# B204D.net
KiCad netlist of a schematic drawn in EAGLE
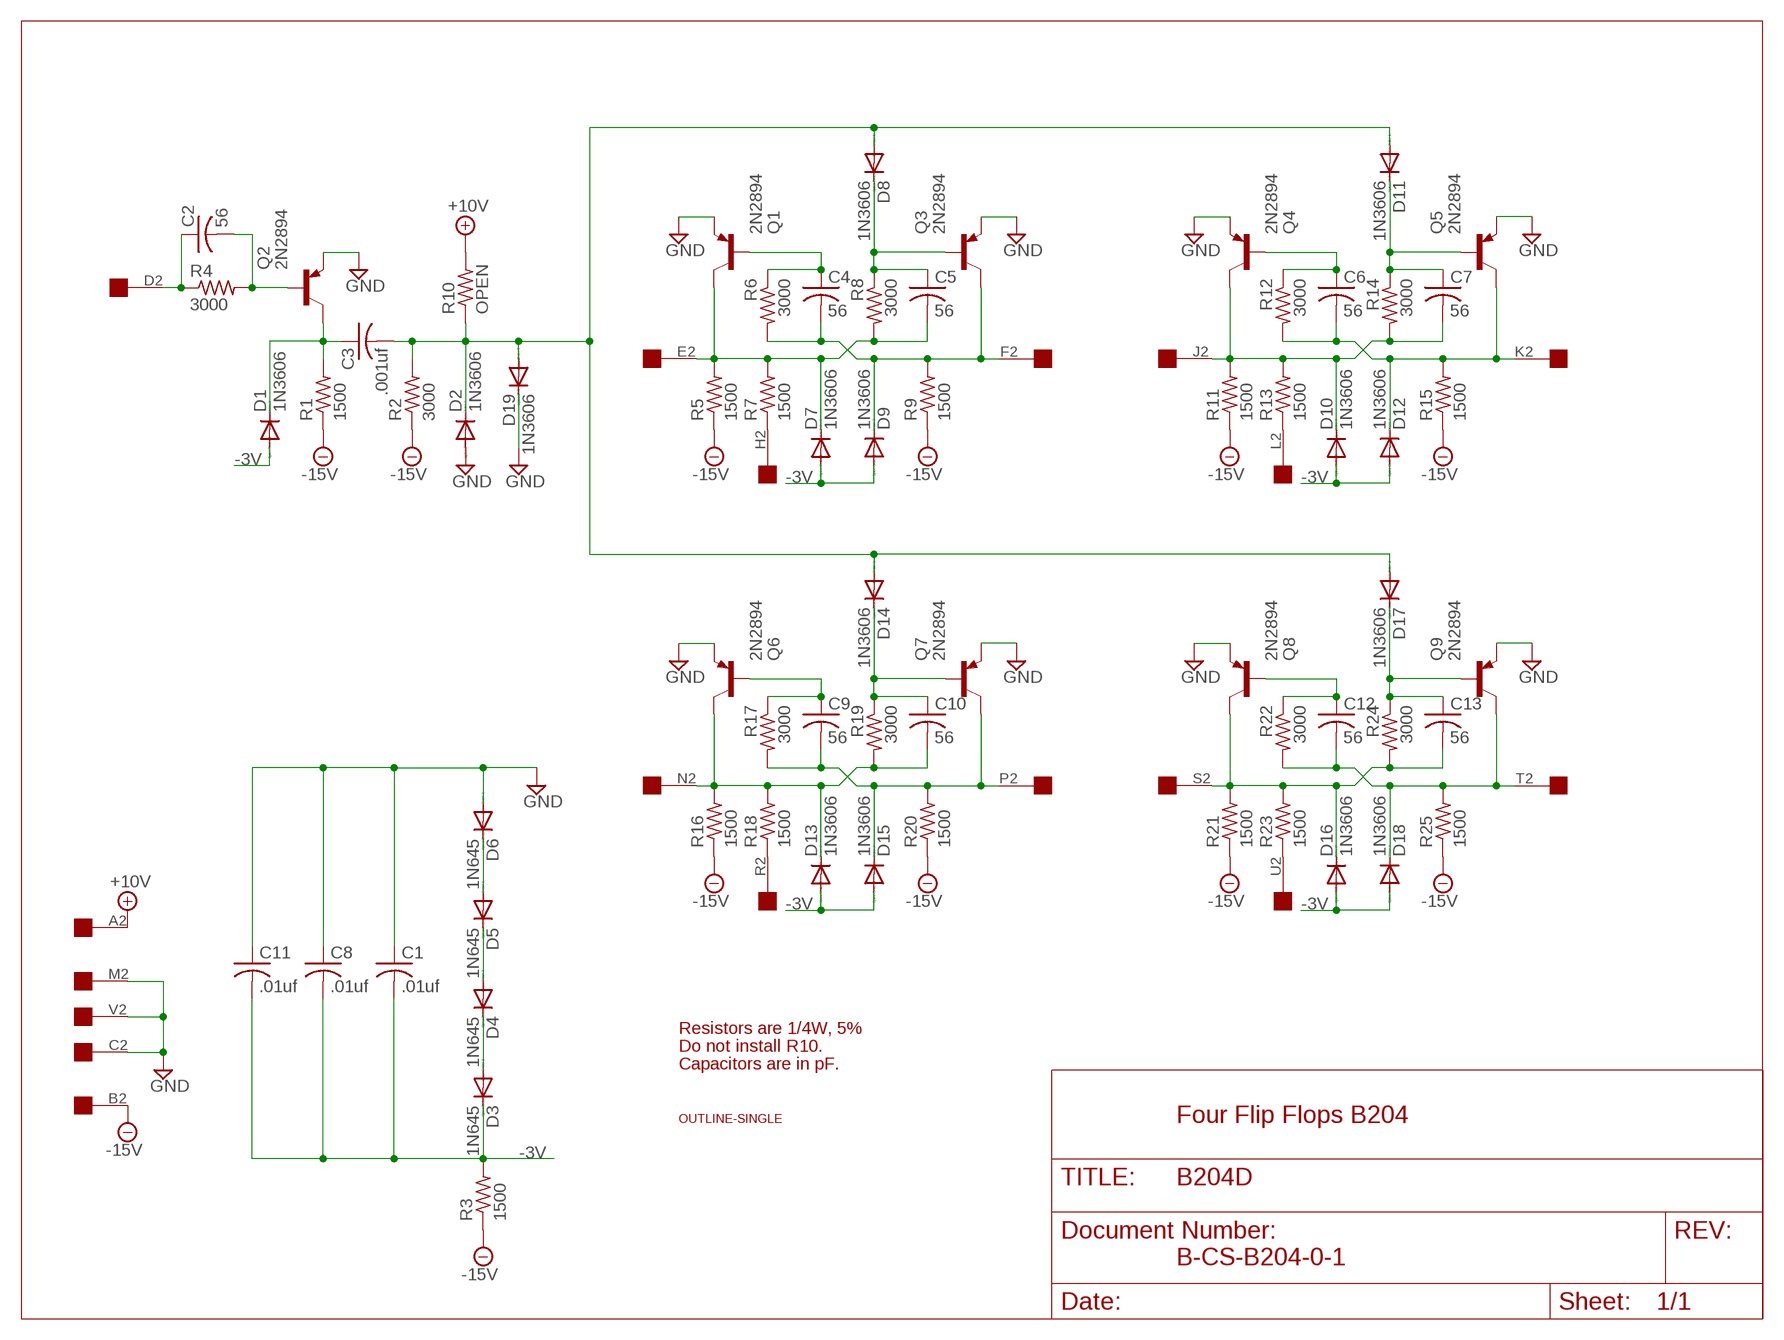
[diagram p0: schematic, sheet 1]

(export (version "E")
  (design (tool "Eeschema 10.0.6"))
  (components
    (comp (ref "C1")
      (value ".01uf")
      (footprint "eagle-import:C050-025X075")
      (libsource (lib "eagle-import") (part "C-US050-025X075"))
    )
    (comp (ref "C2")
      (value "56")
      (footprint "eagle-import:C075-032X103")
      (libsource (lib "eagle-import") (part "C-US075-032X103"))
    )
    (comp (ref "C3")
      (value ".001uf")
      (footprint "eagle-import:C050-025X075")
      (libsource (lib "eagle-import") (part "C-US050-025X075"))
    )
    (comp (ref "C4")
      (value "56")
      (footprint "eagle-import:C075-032X103")
      (libsource (lib "eagle-import") (part "C-US075-032X103"))
    )
    (comp (ref "C5")
      (value "56")
      (footprint "eagle-import:C075-032X103")
      (libsource (lib "eagle-import") (part "C-US075-032X103"))
    )
    (comp (ref "C6")
      (value "56")
      (footprint "eagle-import:C075-032X103")
      (libsource (lib "eagle-import") (part "C-US075-032X103"))
    )
    (comp (ref "C7")
      (value "56")
      (footprint "eagle-import:C075-032X103")
      (libsource (lib "eagle-import") (part "C-US075-032X103"))
    )
    (comp (ref "C8")
      (value ".01uf")
      (footprint "eagle-import:C050-025X075")
      (libsource (lib "eagle-import") (part "C-US050-025X075"))
    )
    (comp (ref "C9")
      (value "56")
      (footprint "eagle-import:C075-032X103")
      (libsource (lib "eagle-import") (part "C-US075-032X103"))
    )
    (comp (ref "C10")
      (value "56")
      (footprint "eagle-import:C075-032X103")
      (libsource (lib "eagle-import") (part "C-US075-032X103"))
    )
    (comp (ref "C11")
      (value ".01uf")
      (footprint "eagle-import:C050-025X075")
      (libsource (lib "eagle-import") (part "C-US050-025X075"))
    )
    (comp (ref "C12")
      (value "56")
      (footprint "eagle-import:C075-032X103")
      (libsource (lib "eagle-import") (part "C-US075-032X103"))
    )
    (comp (ref "C13")
      (value "56")
      (footprint "eagle-import:C075-032X103")
      (libsource (lib "eagle-import") (part "C-US075-032X103"))
    )
    (comp (ref "D1")
      (value "1N3606")
      (footprint "eagle-import:DO35-10")
      (libsource (lib "eagle-import") (part "1N4148DO35-10"))
    )
    (comp (ref "D2")
      (value "1N3606")
      (footprint "eagle-import:DO35-10")
      (libsource (lib "eagle-import") (part "1N4148DO35-10"))
    )
    (comp (ref "D3")
      (value "1N645")
      (footprint "eagle-import:DO35-10")
      (libsource (lib "eagle-import") (part "1N4148DO35-10"))
    )
    (comp (ref "D4")
      (value "1N645")
      (footprint "eagle-import:DO35-10")
      (libsource (lib "eagle-import") (part "1N4148DO35-10"))
    )
    (comp (ref "D5")
      (value "1N645")
      (footprint "eagle-import:DO35-10")
      (libsource (lib "eagle-import") (part "1N4148DO35-10"))
    )
    (comp (ref "D6")
      (value "1N645")
      (footprint "eagle-import:DO35-10")
      (libsource (lib "eagle-import") (part "1N4148DO35-10"))
    )
    (comp (ref "D7")
      (value "1N3606")
      (footprint "eagle-import:DO35-10")
      (libsource (lib "eagle-import") (part "1N4148DO35-10"))
    )
    (comp (ref "D8")
      (value "1N3606")
      (footprint "eagle-import:DO35-10")
      (libsource (lib "eagle-import") (part "1N4148DO35-10"))
    )
    (comp (ref "D9")
      (value "1N3606")
      (footprint "eagle-import:DO35-10")
      (libsource (lib "eagle-import") (part "1N4148DO35-10"))
    )
    (comp (ref "D10")
      (value "1N3606")
      (footprint "eagle-import:DO35-10")
      (libsource (lib "eagle-import") (part "1N4148DO35-10"))
    )
    (comp (ref "D11")
      (value "1N3606")
      (footprint "eagle-import:DO35-10")
      (libsource (lib "eagle-import") (part "1N4148DO35-10"))
    )
    (comp (ref "D12")
      (value "1N3606")
      (footprint "eagle-import:DO35-10")
      (libsource (lib "eagle-import") (part "1N4148DO35-10"))
    )
    (comp (ref "D13")
      (value "1N3606")
      (footprint "eagle-import:DO35-10")
      (libsource (lib "eagle-import") (part "1N4148DO35-10"))
    )
    (comp (ref "D14")
      (value "1N3606")
      (footprint "eagle-import:DO35-10")
      (libsource (lib "eagle-import") (part "1N4148DO35-10"))
    )
    (comp (ref "D15")
      (value "1N3606")
      (footprint "eagle-import:DO35-10")
      (libsource (lib "eagle-import") (part "1N4148DO35-10"))
    )
    (comp (ref "D16")
      (value "1N3606")
      (footprint "eagle-import:DO35-10")
      (libsource (lib "eagle-import") (part "1N4148DO35-10"))
    )
    (comp (ref "D17")
      (value "1N3606")
      (footprint "eagle-import:DO35-10")
      (libsource (lib "eagle-import") (part "1N4148DO35-10"))
    )
    (comp (ref "D18")
      (value "1N3606")
      (footprint "eagle-import:DO35-10")
      (libsource (lib "eagle-import") (part "1N4148DO35-10"))
    )
    (comp (ref "D19")
      (value "1N3606")
      (footprint "eagle-import:DO35-10")
      (libsource (lib "eagle-import") (part "1N4148DO35-10"))
    )
    (comp (ref "Q1")
      (value "2N2894")
      (footprint "eagle-import:TO39")
      (libsource (lib "eagle-import") (part "2N3637"))
    )
    (comp (ref "Q2")
      (value "2N2894")
      (footprint "eagle-import:TO39")
      (libsource (lib "eagle-import") (part "2N3637"))
    )
    (comp (ref "Q3")
      (value "2N2894")
      (footprint "eagle-import:TO39")
      (libsource (lib "eagle-import") (part "2N3637"))
    )
    (comp (ref "Q4")
      (value "2N2894")
      (footprint "eagle-import:TO39")
      (libsource (lib "eagle-import") (part "2N3637"))
    )
    (comp (ref "Q5")
      (value "2N2894")
      (footprint "eagle-import:TO39")
      (libsource (lib "eagle-import") (part "2N3637"))
    )
    (comp (ref "Q6")
      (value "2N2894")
      (footprint "eagle-import:TO39")
      (libsource (lib "eagle-import") (part "2N3637"))
    )
    (comp (ref "Q7")
      (value "2N2894")
      (footprint "eagle-import:TO39")
      (libsource (lib "eagle-import") (part "2N3637"))
    )
    (comp (ref "Q8")
      (value "2N2894")
      (footprint "eagle-import:TO39")
      (libsource (lib "eagle-import") (part "2N3637"))
    )
    (comp (ref "Q9")
      (value "2N2894")
      (footprint "eagle-import:TO39")
      (libsource (lib "eagle-import") (part "2N3637"))
    )
    (comp (ref "R1")
      (value "1500")
      (footprint "eagle-import:0207_10")
      (libsource (lib "eagle-import") (part "R-US_0207/10"))
    )
    (comp (ref "R2")
      (value "3000")
      (footprint "eagle-import:0207_10")
      (libsource (lib "eagle-import") (part "R-US_0207/10"))
    )
    (comp (ref "R3")
      (value "1500")
      (footprint "eagle-import:0207_10")
      (libsource (lib "eagle-import") (part "R-US_0207/10"))
    )
    (comp (ref "R4")
      (value "3000")
      (footprint "eagle-import:0207_10")
      (libsource (lib "eagle-import") (part "R-US_0207/10"))
    )
    (comp (ref "R5")
      (value "1500")
      (footprint "eagle-import:0207_10")
      (libsource (lib "eagle-import") (part "R-US_0207/10"))
    )
    (comp (ref "R6")
      (value "3000")
      (footprint "eagle-import:0207_10")
      (libsource (lib "eagle-import") (part "R-US_0207/10"))
    )
    (comp (ref "R7")
      (value "1500")
      (footprint "eagle-import:0207_10")
      (libsource (lib "eagle-import") (part "R-US_0207/10"))
    )
    (comp (ref "R8")
      (value "3000")
      (footprint "eagle-import:0207_10")
      (libsource (lib "eagle-import") (part "R-US_0207/10"))
    )
    (comp (ref "R9")
      (value "1500")
      (footprint "eagle-import:0207_10")
      (libsource (lib "eagle-import") (part "R-US_0207/10"))
    )
    (comp (ref "R10")
      (value "OPEN")
      (footprint "eagle-import:0207_10")
      (libsource (lib "eagle-import") (part "R-US_0207/10"))
    )
    (comp (ref "R11")
      (value "1500")
      (footprint "eagle-import:0207_10")
      (libsource (lib "eagle-import") (part "R-US_0207/10"))
    )
    (comp (ref "R12")
      (value "3000")
      (footprint "eagle-import:0207_10")
      (libsource (lib "eagle-import") (part "R-US_0207/10"))
    )
    (comp (ref "R13")
      (value "1500")
      (footprint "eagle-import:0207_10")
      (libsource (lib "eagle-import") (part "R-US_0207/10"))
    )
    (comp (ref "R14")
      (value "3000")
      (footprint "eagle-import:0207_10")
      (libsource (lib "eagle-import") (part "R-US_0207/10"))
    )
    (comp (ref "R15")
      (value "1500")
      (footprint "eagle-import:0207_10")
      (libsource (lib "eagle-import") (part "R-US_0207/10"))
    )
    (comp (ref "R16")
      (value "1500")
      (footprint "eagle-import:0207_10")
      (libsource (lib "eagle-import") (part "R-US_0207/10"))
    )
    (comp (ref "R17")
      (value "3000")
      (footprint "eagle-import:0207_10")
      (libsource (lib "eagle-import") (part "R-US_0207/10"))
    )
    (comp (ref "R18")
      (value "1500")
      (footprint "eagle-import:0207_10")
      (libsource (lib "eagle-import") (part "R-US_0207/10"))
    )
    (comp (ref "R19")
      (value "3000")
      (footprint "eagle-import:0207_10")
      (libsource (lib "eagle-import") (part "R-US_0207/10"))
    )
    (comp (ref "R20")
      (value "1500")
      (footprint "eagle-import:0207_10")
      (libsource (lib "eagle-import") (part "R-US_0207/10"))
    )
    (comp (ref "R21")
      (value "1500")
      (footprint "eagle-import:0207_10")
      (libsource (lib "eagle-import") (part "R-US_0207/10"))
    )
    (comp (ref "R22")
      (value "3000")
      (footprint "eagle-import:0207_10")
      (libsource (lib "eagle-import") (part "R-US_0207/10"))
    )
    (comp (ref "R23")
      (value "1500")
      (footprint "eagle-import:0207_10")
      (libsource (lib "eagle-import") (part "R-US_0207/10"))
    )
    (comp (ref "R24")
      (value "3000")
      (footprint "eagle-import:0207_10")
      (libsource (lib "eagle-import") (part "R-US_0207/10"))
    )
    (comp (ref "R25")
      (value "1500")
      (footprint "eagle-import:0207_10")
      (libsource (lib "eagle-import") (part "R-US_0207/10"))
    )
    (comp (ref "U$1")
      (value "OUTLINE-SINGLE")
      (footprint "eagle-import:SINGLE")
      (libsource (lib "eagle-import") (part "OUTLINE-SINGLE"))
    )
    (comp (ref "U$2")
      (value "EDGE-1")
      (footprint "eagle-import:EDGE-CON1")
      (libsource (lib "eagle-import") (part "EDGE-1"))
    )
  )
  (nets
    (net (code "1") (name "+10V") (class "Default")
      (node (ref "R10") (pin "2") (pinfunction "2_2") (pintype "passive"))
      (node (ref "U$2") (pin "A2") (pinfunction "1_A2") (pintype "bidirectional"))
    )
    (net (code "2") (name "-15V") (class "Default")
      (node (ref "R1") (pin "1") (pinfunction "1_1") (pintype "passive"))
      (node (ref "R11") (pin "1") (pinfunction "1_1") (pintype "passive"))
      (node (ref "R15") (pin "1") (pinfunction "1_1") (pintype "passive"))
      (node (ref "R16") (pin "1") (pinfunction "1_1") (pintype "passive"))
      (node (ref "R2") (pin "1") (pinfunction "1_1") (pintype "passive"))
      (node (ref "R20") (pin "1") (pinfunction "1_1") (pintype "passive"))
      (node (ref "R21") (pin "1") (pinfunction "1_1") (pintype "passive"))
      (node (ref "R25") (pin "1") (pinfunction "1_1") (pintype "passive"))
      (node (ref "R3") (pin "1") (pinfunction "1_1") (pintype "passive"))
      (node (ref "R5") (pin "1") (pinfunction "1_1") (pintype "passive"))
      (node (ref "R9") (pin "1") (pinfunction "1_1") (pintype "passive"))
      (node (ref "U$2") (pin "B2") (pinfunction "1_B2") (pintype "bidirectional"))
    )
    (net (code "3") (name "/-3V") (class "Default")
      (node (ref "C1") (pin "2") (pinfunction "2_2") (pintype "passive"))
      (node (ref "C11") (pin "2") (pinfunction "2_2") (pintype "passive"))
      (node (ref "C8") (pin "2") (pinfunction "2_2") (pintype "passive"))
      (node (ref "D1") (pin "A") (pinfunction "A_A") (pintype "passive"))
      (node (ref "D10") (pin "A") (pinfunction "A_A") (pintype "passive"))
      (node (ref "D12") (pin "A") (pinfunction "A_A") (pintype "passive"))
      (node (ref "D13") (pin "A") (pinfunction "A_A") (pintype "passive"))
      (node (ref "D15") (pin "A") (pinfunction "A_A") (pintype "passive"))
      (node (ref "D16") (pin "A") (pinfunction "A_A") (pintype "passive"))
      (node (ref "D18") (pin "A") (pinfunction "A_A") (pintype "passive"))
      (node (ref "D3") (pin "C") (pinfunction "C_C") (pintype "passive"))
      (node (ref "D7") (pin "A") (pinfunction "A_A") (pintype "passive"))
      (node (ref "D9") (pin "A") (pinfunction "A_A") (pintype "passive"))
      (node (ref "R3") (pin "2") (pinfunction "2_2") (pintype "passive"))
    )
    (net (code "4") (name "GND") (class "Default")
      (node (ref "C1") (pin "1") (pinfunction "1_1") (pintype "passive"))
      (node (ref "C11") (pin "1") (pinfunction "1_1") (pintype "passive"))
      (node (ref "C8") (pin "1") (pinfunction "1_1") (pintype "passive"))
      (node (ref "D19") (pin "C") (pinfunction "C_C") (pintype "passive"))
      (node (ref "D2") (pin "A") (pinfunction "A_A") (pintype "passive"))
      (node (ref "D6") (pin "A") (pinfunction "A_A") (pintype "passive"))
      (node (ref "Q1") (pin "1") (pinfunction "E_1") (pintype "passive"))
      (node (ref "Q2") (pin "1") (pinfunction "E_1") (pintype "passive"))
      (node (ref "Q3") (pin "1") (pinfunction "E_1") (pintype "passive"))
      (node (ref "Q4") (pin "1") (pinfunction "E_1") (pintype "passive"))
      (node (ref "Q5") (pin "1") (pinfunction "E_1") (pintype "passive"))
      (node (ref "Q6") (pin "1") (pinfunction "E_1") (pintype "passive"))
      (node (ref "Q7") (pin "1") (pinfunction "E_1") (pintype "passive"))
      (node (ref "Q8") (pin "1") (pinfunction "E_1") (pintype "passive"))
      (node (ref "Q9") (pin "1") (pinfunction "E_1") (pintype "passive"))
      (node (ref "U$2") (pin "C2") (pinfunction "1_C2") (pintype "bidirectional"))
      (node (ref "U$2") (pin "M2") (pinfunction "1_M2") (pintype "bidirectional"))
      (node (ref "U$2") (pin "V2") (pinfunction "1_V2") (pintype "bidirectional"))
    )
    (net (code "5") (name "Net-(C3-Pad2)") (class "Default")
      (node (ref "C3") (pin "2") (pinfunction "2_2") (pintype "passive"))
      (node (ref "D11") (pin "A") (pinfunction "A_A") (pintype "passive"))
      (node (ref "D14") (pin "A") (pinfunction "A_A") (pintype "passive"))
      (node (ref "D17") (pin "A") (pinfunction "A_A") (pintype "passive"))
      (node (ref "D19") (pin "A") (pinfunction "A_A") (pintype "passive"))
      (node (ref "D2") (pin "C") (pinfunction "C_C") (pintype "passive"))
      (node (ref "D8") (pin "A") (pinfunction "A_A") (pintype "passive"))
      (node (ref "R10") (pin "1") (pinfunction "1_1") (pintype "passive"))
      (node (ref "R2") (pin "2") (pinfunction "2_2") (pintype "passive"))
    )
    (net (code "6") (name "Net-(D3-PadA)") (class "Default")
      (node (ref "D3") (pin "A") (pinfunction "A_A") (pintype "passive"))
      (node (ref "D4") (pin "C") (pinfunction "C_C") (pintype "passive"))
    )
    (net (code "7") (name "Net-(D4-PadA)") (class "Default")
      (node (ref "D4") (pin "A") (pinfunction "A_A") (pintype "passive"))
      (node (ref "D5") (pin "C") (pinfunction "C_C") (pintype "passive"))
    )
    (net (code "8") (name "Net-(D5-PadA)") (class "Default")
      (node (ref "D5") (pin "A") (pinfunction "A_A") (pintype "passive"))
      (node (ref "D6") (pin "C") (pinfunction "C_C") (pintype "passive"))
    )
    (net (code "9") (name "Net-(Q1-B)") (class "Default")
      (node (ref "C4") (pin "1") (pinfunction "1_1") (pintype "passive"))
      (node (ref "Q1") (pin "2") (pinfunction "B_2") (pintype "passive"))
      (node (ref "R6") (pin "1") (pinfunction "1_1") (pintype "passive"))
    )
    (net (code "10") (name "Net-(Q1-C)") (class "Default")
      (node (ref "C5") (pin "2") (pinfunction "2_2") (pintype "passive"))
      (node (ref "D7") (pin "C") (pinfunction "C_C") (pintype "passive"))
      (node (ref "Q1") (pin "3") (pinfunction "C_3") (pintype "passive"))
      (node (ref "R5") (pin "2") (pinfunction "2_2") (pintype "passive"))
      (node (ref "R7") (pin "2") (pinfunction "2_2") (pintype "passive"))
      (node (ref "R8") (pin "2") (pinfunction "2_2") (pintype "passive"))
      (node (ref "U$2") (pin "E2") (pinfunction "1_E2") (pintype "bidirectional"))
    )
    (net (code "11") (name "Net-(Q2-B)") (class "Default")
      (node (ref "C2") (pin "2") (pinfunction "2_2") (pintype "passive"))
      (node (ref "Q2") (pin "2") (pinfunction "B_2") (pintype "passive"))
      (node (ref "R4") (pin "2") (pinfunction "2_2") (pintype "passive"))
    )
    (net (code "12") (name "Net-(Q2-C)") (class "Default")
      (node (ref "C3") (pin "1") (pinfunction "1_1") (pintype "passive"))
      (node (ref "D1") (pin "C") (pinfunction "C_C") (pintype "passive"))
      (node (ref "Q2") (pin "3") (pinfunction "C_3") (pintype "passive"))
      (node (ref "R1") (pin "2") (pinfunction "2_2") (pintype "passive"))
    )
    (net (code "13") (name "Net-(Q3-B)") (class "Default")
      (node (ref "C5") (pin "1") (pinfunction "1_1") (pintype "passive"))
      (node (ref "D8") (pin "C") (pinfunction "C_C") (pintype "passive"))
      (node (ref "Q3") (pin "2") (pinfunction "B_2") (pintype "passive"))
      (node (ref "R8") (pin "1") (pinfunction "1_1") (pintype "passive"))
    )
    (net (code "14") (name "Net-(Q3-C)") (class "Default")
      (node (ref "C4") (pin "2") (pinfunction "2_2") (pintype "passive"))
      (node (ref "D9") (pin "C") (pinfunction "C_C") (pintype "passive"))
      (node (ref "Q3") (pin "3") (pinfunction "C_3") (pintype "passive"))
      (node (ref "R6") (pin "2") (pinfunction "2_2") (pintype "passive"))
      (node (ref "R9") (pin "2") (pinfunction "2_2") (pintype "passive"))
      (node (ref "U$2") (pin "F2") (pinfunction "1_F2") (pintype "bidirectional"))
    )
    (net (code "15") (name "Net-(Q4-B)") (class "Default")
      (node (ref "C6") (pin "1") (pinfunction "1_1") (pintype "passive"))
      (node (ref "Q4") (pin "2") (pinfunction "B_2") (pintype "passive"))
      (node (ref "R12") (pin "1") (pinfunction "1_1") (pintype "passive"))
    )
    (net (code "16") (name "Net-(Q4-C)") (class "Default")
      (node (ref "C7") (pin "2") (pinfunction "2_2") (pintype "passive"))
      (node (ref "D10") (pin "C") (pinfunction "C_C") (pintype "passive"))
      (node (ref "Q4") (pin "3") (pinfunction "C_3") (pintype "passive"))
      (node (ref "R11") (pin "2") (pinfunction "2_2") (pintype "passive"))
      (node (ref "R13") (pin "2") (pinfunction "2_2") (pintype "passive"))
      (node (ref "R14") (pin "2") (pinfunction "2_2") (pintype "passive"))
      (node (ref "U$2") (pin "J2") (pinfunction "1_J2") (pintype "bidirectional"))
    )
    (net (code "17") (name "Net-(Q5-B)") (class "Default")
      (node (ref "C7") (pin "1") (pinfunction "1_1") (pintype "passive"))
      (node (ref "D11") (pin "C") (pinfunction "C_C") (pintype "passive"))
      (node (ref "Q5") (pin "2") (pinfunction "B_2") (pintype "passive"))
      (node (ref "R14") (pin "1") (pinfunction "1_1") (pintype "passive"))
    )
    (net (code "18") (name "Net-(Q5-C)") (class "Default")
      (node (ref "C6") (pin "2") (pinfunction "2_2") (pintype "passive"))
      (node (ref "D12") (pin "C") (pinfunction "C_C") (pintype "passive"))
      (node (ref "Q5") (pin "3") (pinfunction "C_3") (pintype "passive"))
      (node (ref "R12") (pin "2") (pinfunction "2_2") (pintype "passive"))
      (node (ref "R15") (pin "2") (pinfunction "2_2") (pintype "passive"))
      (node (ref "U$2") (pin "K2") (pinfunction "1_K2") (pintype "bidirectional"))
    )
    (net (code "19") (name "Net-(Q6-B)") (class "Default")
      (node (ref "C9") (pin "1") (pinfunction "1_1") (pintype "passive"))
      (node (ref "Q6") (pin "2") (pinfunction "B_2") (pintype "passive"))
      (node (ref "R17") (pin "1") (pinfunction "1_1") (pintype "passive"))
    )
    (net (code "20") (name "Net-(Q6-C)") (class "Default")
      (node (ref "C10") (pin "2") (pinfunction "2_2") (pintype "passive"))
      (node (ref "D13") (pin "C") (pinfunction "C_C") (pintype "passive"))
      (node (ref "Q6") (pin "3") (pinfunction "C_3") (pintype "passive"))
      (node (ref "R16") (pin "2") (pinfunction "2_2") (pintype "passive"))
      (node (ref "R18") (pin "2") (pinfunction "2_2") (pintype "passive"))
      (node (ref "R19") (pin "2") (pinfunction "2_2") (pintype "passive"))
      (node (ref "U$2") (pin "N2") (pinfunction "1_N2") (pintype "bidirectional"))
    )
    (net (code "21") (name "Net-(Q7-B)") (class "Default")
      (node (ref "C10") (pin "1") (pinfunction "1_1") (pintype "passive"))
      (node (ref "D14") (pin "C") (pinfunction "C_C") (pintype "passive"))
      (node (ref "Q7") (pin "2") (pinfunction "B_2") (pintype "passive"))
      (node (ref "R19") (pin "1") (pinfunction "1_1") (pintype "passive"))
    )
    (net (code "22") (name "Net-(Q7-C)") (class "Default")
      (node (ref "C9") (pin "2") (pinfunction "2_2") (pintype "passive"))
      (node (ref "D15") (pin "C") (pinfunction "C_C") (pintype "passive"))
      (node (ref "Q7") (pin "3") (pinfunction "C_3") (pintype "passive"))
      (node (ref "R17") (pin "2") (pinfunction "2_2") (pintype "passive"))
      (node (ref "R20") (pin "2") (pinfunction "2_2") (pintype "passive"))
      (node (ref "U$2") (pin "P2") (pinfunction "1_P2") (pintype "bidirectional"))
    )
    (net (code "23") (name "Net-(Q8-B)") (class "Default")
      (node (ref "C12") (pin "1") (pinfunction "1_1") (pintype "passive"))
      (node (ref "Q8") (pin "2") (pinfunction "B_2") (pintype "passive"))
      (node (ref "R22") (pin "1") (pinfunction "1_1") (pintype "passive"))
    )
    (net (code "24") (name "Net-(Q8-C)") (class "Default")
      (node (ref "C13") (pin "2") (pinfunction "2_2") (pintype "passive"))
      (node (ref "D16") (pin "C") (pinfunction "C_C") (pintype "passive"))
      (node (ref "Q8") (pin "3") (pinfunction "C_3") (pintype "passive"))
      (node (ref "R21") (pin "2") (pinfunction "2_2") (pintype "passive"))
      (node (ref "R23") (pin "2") (pinfunction "2_2") (pintype "passive"))
      (node (ref "R24") (pin "2") (pinfunction "2_2") (pintype "passive"))
      (node (ref "U$2") (pin "S2") (pinfunction "1_S2") (pintype "bidirectional"))
    )
    (net (code "25") (name "Net-(Q9-B)") (class "Default")
      (node (ref "C13") (pin "1") (pinfunction "1_1") (pintype "passive"))
      (node (ref "D17") (pin "C") (pinfunction "C_C") (pintype "passive"))
      (node (ref "Q9") (pin "2") (pinfunction "B_2") (pintype "passive"))
      (node (ref "R24") (pin "1") (pinfunction "1_1") (pintype "passive"))
    )
    (net (code "26") (name "Net-(Q9-C)") (class "Default")
      (node (ref "C12") (pin "2") (pinfunction "2_2") (pintype "passive"))
      (node (ref "D18") (pin "C") (pinfunction "C_C") (pintype "passive"))
      (node (ref "Q9") (pin "3") (pinfunction "C_3") (pintype "passive"))
      (node (ref "R22") (pin "2") (pinfunction "2_2") (pintype "passive"))
      (node (ref "R25") (pin "2") (pinfunction "2_2") (pintype "passive"))
      (node (ref "U$2") (pin "T2") (pinfunction "1_T2") (pintype "bidirectional"))
    )
    (net (code "27") (name "Net-(U$2D-1)") (class "Default")
      (node (ref "C2") (pin "1") (pinfunction "1_1") (pintype "passive"))
      (node (ref "R4") (pin "1") (pinfunction "1_1") (pintype "passive"))
      (node (ref "U$2") (pin "D2") (pinfunction "1_D2") (pintype "bidirectional"))
    )
    (net (code "28") (name "Net-(U$2G-1)") (class "Default")
      (node (ref "R7") (pin "1") (pinfunction "1_1") (pintype "passive"))
      (node (ref "U$2") (pin "H2") (pinfunction "1_H2") (pintype "bidirectional"))
    )
    (net (code "29") (name "Net-(U$2J-1)") (class "Default")
      (node (ref "R13") (pin "1") (pinfunction "1_1") (pintype "passive"))
      (node (ref "U$2") (pin "L2") (pinfunction "1_L2") (pintype "bidirectional"))
    )
    (net (code "30") (name "Net-(U$2N-1)") (class "Default")
      (node (ref "R18") (pin "1") (pinfunction "1_1") (pintype "passive"))
      (node (ref "U$2") (pin "R2") (pinfunction "1_R2") (pintype "bidirectional"))
    )
    (net (code "31") (name "Net-(U$2Q-1)") (class "Default")
      (node (ref "R23") (pin "1") (pinfunction "1_1") (pintype "passive"))
      (node (ref "U$2") (pin "U2") (pinfunction "1_U2") (pintype "bidirectional"))
    )
  )
)
